# ChargerTimer_V3hack.net
KiCad netlist of a schematic drawn in EAGLE
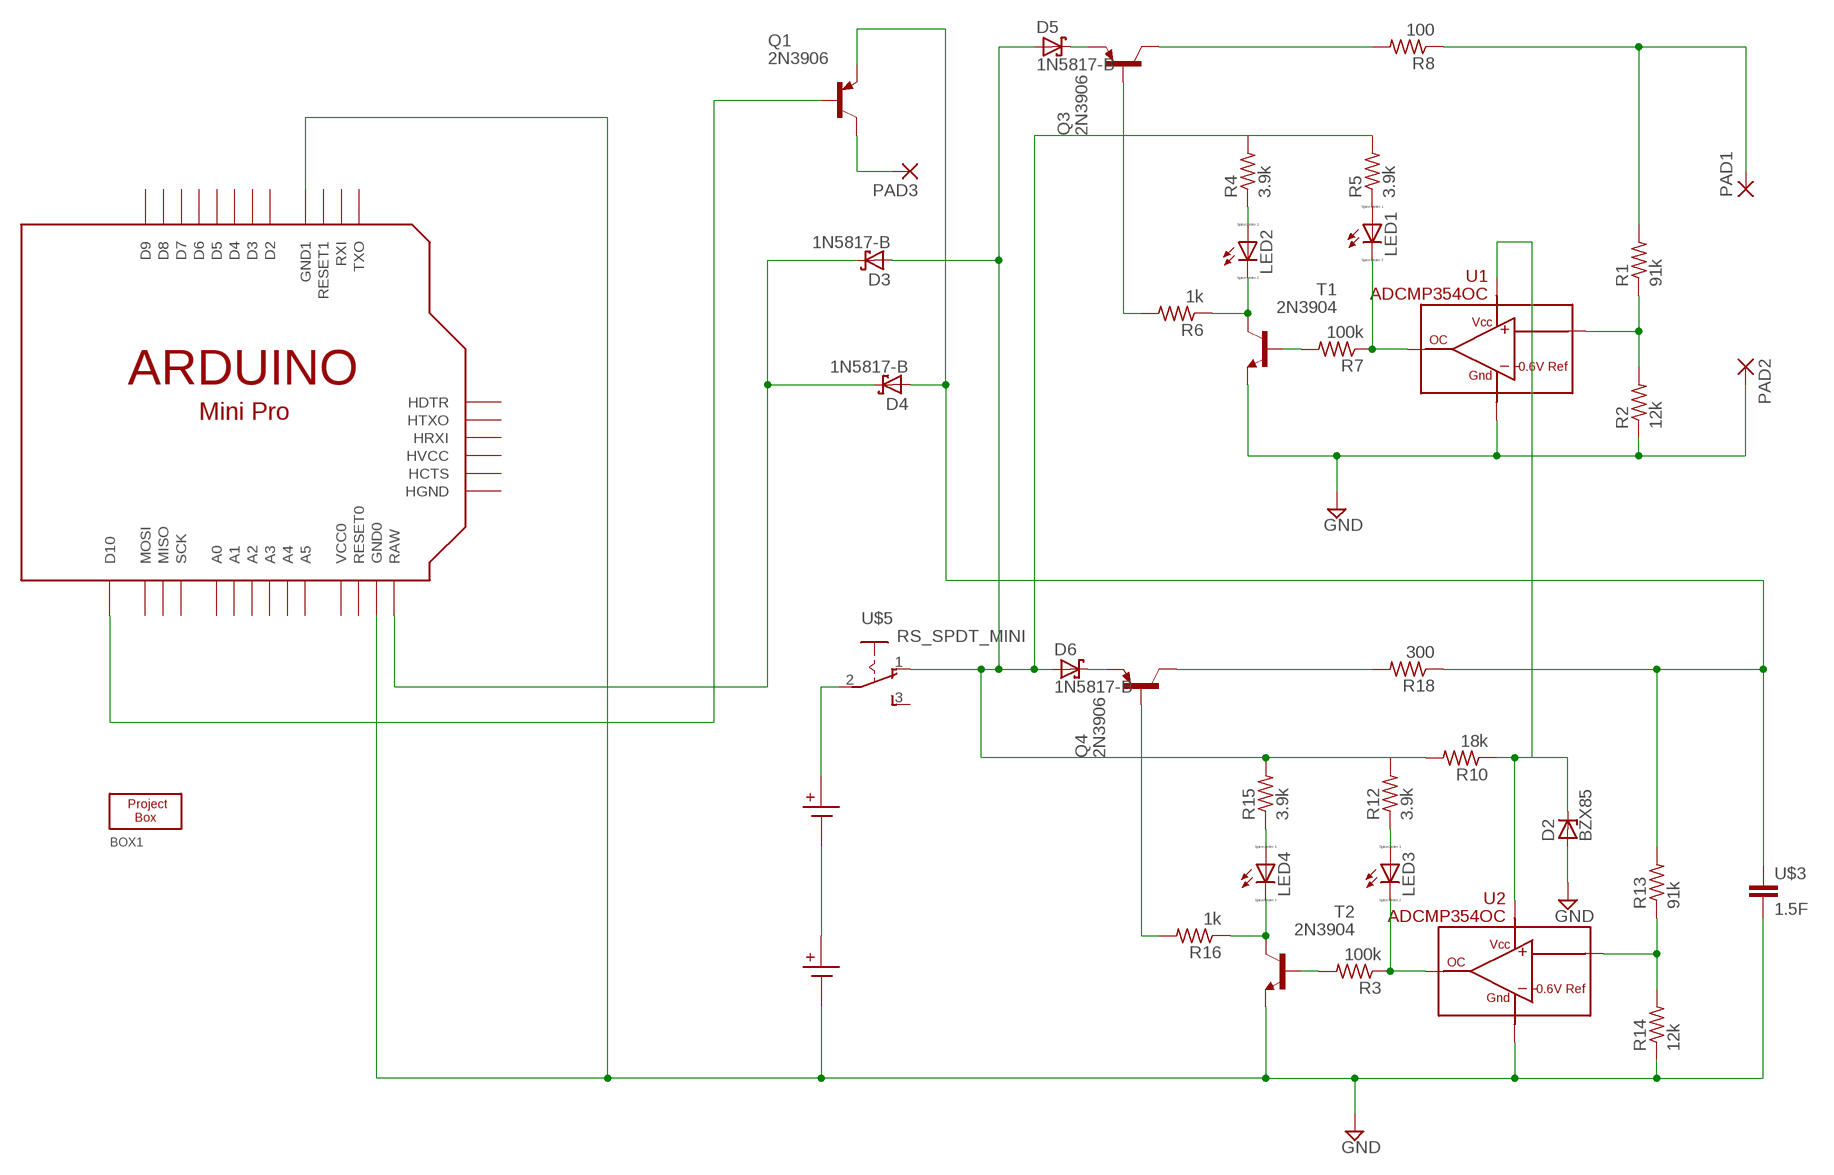
[diagram p0: schematic, sheet 1]

(export (version "E")
  (design (tool "Eeschema 10.0.6"))
  (components
    (comp (ref "BOX1")
      (value "RS_BOX_4IN")
      (footprint "eagle-import:RS_BOX_OUTLINE_4IN")
      (libsource (lib "eagle-import") (part "RS_BOX_4IN"))
    )
    (comp (ref "D2")
      (value "BZX85")
      (footprint "eagle-import:DO41Z10")
      (libsource (lib "eagle-import") (part "BZX85"))
    )
    (comp (ref "D3")
      (value "1N5817-B")
      (footprint "eagle-import:DO41-7.6")
      (libsource (lib "eagle-import") (part "1N5817-B"))
    )
    (comp (ref "D4")
      (value "1N5817-B")
      (footprint "eagle-import:DO41-7.6")
      (libsource (lib "eagle-import") (part "1N5817-B"))
    )
    (comp (ref "D5")
      (value "1N5817-B")
      (footprint "eagle-import:DO41-7.6")
      (libsource (lib "eagle-import") (part "1N5817-B"))
    )
    (comp (ref "D6")
      (value "1N5817-B")
      (footprint "eagle-import:DO41-7.6")
      (libsource (lib "eagle-import") (part "1N5817-B"))
    )
    (comp (ref "LED1")
      (value "LED_ELD260")
      (footprint "eagle-import:LED_LD260")
      (libsource (lib "eagle-import") (part "LED_ELD260"))
    )
    (comp (ref "LED2")
      (value "LED_ELD260")
      (footprint "eagle-import:LED_LD260")
      (libsource (lib "eagle-import") (part "LED_ELD260"))
    )
    (comp (ref "LED3")
      (value "LED_ELD260")
      (footprint "eagle-import:LED_LD260")
      (libsource (lib "eagle-import") (part "LED_ELD260"))
    )
    (comp (ref "LED4")
      (value "LED_ELD260")
      (footprint "eagle-import:LED_LD260")
      (libsource (lib "eagle-import") (part "LED_ELD260"))
    )
    (comp (ref "PAD1")
      (value "2,15/1,0")
      (footprint "eagle-import:2,15_1,0")
      (libsource (lib "eagle-import") (part "2,15/1,0"))
    )
    (comp (ref "PAD2")
      (value "2,15/1,0")
      (footprint "eagle-import:2,15_1,0")
      (libsource (lib "eagle-import") (part "2,15/1,0"))
    )
    (comp (ref "PAD3")
      (value "2,15/1,0")
      (footprint "eagle-import:2,15_1,0")
      (libsource (lib "eagle-import") (part "2,15/1,0"))
    )
    (comp (ref "Q1")
      (value "2N3906")
      (footprint "eagle-import:TO92")
      (libsource (lib "eagle-import") (part "2N3906"))
    )
    (comp (ref "Q3")
      (value "2N3906")
      (footprint "eagle-import:TO92")
      (libsource (lib "eagle-import") (part "2N3906"))
    )
    (comp (ref "Q4")
      (value "2N3906")
      (footprint "eagle-import:TO92")
      (libsource (lib "eagle-import") (part "2N3906"))
    )
    (comp (ref "R1")
      (value "91k")
      (footprint "eagle-import:0207_7")
      (libsource (lib "eagle-import") (part "R-US_0207/7"))
    )
    (comp (ref "R2")
      (value "12k")
      (footprint "eagle-import:0207_7")
      (libsource (lib "eagle-import") (part "R-US_0207/7"))
    )
    (comp (ref "R3")
      (value "100k")
      (footprint "eagle-import:0207_7")
      (libsource (lib "eagle-import") (part "R-US_0207/7"))
    )
    (comp (ref "R4")
      (value "3.9k")
      (footprint "eagle-import:0207_7")
      (libsource (lib "eagle-import") (part "R-US_0207/7"))
    )
    (comp (ref "R5")
      (value "3.9k")
      (footprint "eagle-import:0207_7")
      (libsource (lib "eagle-import") (part "R-US_0207/7"))
    )
    (comp (ref "R6")
      (value "1k")
      (footprint "eagle-import:0207_7")
      (libsource (lib "eagle-import") (part "R-US_0207/7"))
    )
    (comp (ref "R7")
      (value "100k")
      (footprint "eagle-import:0207_7")
      (libsource (lib "eagle-import") (part "R-US_0207/7"))
    )
    (comp (ref "R8")
      (value "100")
      (footprint "eagle-import:0207_7")
      (libsource (lib "eagle-import") (part "R-US_0207/7"))
    )
    (comp (ref "R10")
      (value "18k")
      (footprint "eagle-import:0207_7")
      (libsource (lib "eagle-import") (part "R-US_0207/7"))
    )
    (comp (ref "R12")
      (value "3.9k")
      (footprint "eagle-import:0207_7")
      (libsource (lib "eagle-import") (part "R-US_0207/7"))
    )
    (comp (ref "R13")
      (value "91k")
      (footprint "eagle-import:0207_7")
      (libsource (lib "eagle-import") (part "R-US_0207/7"))
    )
    (comp (ref "R14")
      (value "12k")
      (footprint "eagle-import:0207_7")
      (libsource (lib "eagle-import") (part "R-US_0207/7"))
    )
    (comp (ref "R15")
      (value "3.9k")
      (footprint "eagle-import:0207_7")
      (libsource (lib "eagle-import") (part "R-US_0207/7"))
    )
    (comp (ref "R16")
      (value "1k")
      (footprint "eagle-import:0207_7")
      (libsource (lib "eagle-import") (part "R-US_0207/7"))
    )
    (comp (ref "R18")
      (value "300")
      (footprint "eagle-import:0207_7")
      (libsource (lib "eagle-import") (part "R-US_0207/7"))
    )
    (comp (ref "T1")
      (value "2N3904")
      (footprint "eagle-import:TO92")
      (libsource (lib "eagle-import") (part "2N3904"))
    )
    (comp (ref "T2")
      (value "2N3904")
      (footprint "eagle-import:TO92")
      (libsource (lib "eagle-import") (part "2N3904"))
    )
    (comp (ref "U$1")
      (value "BH1000G")
      (footprint "eagle-import:BH1000G")
      (libsource (lib "eagle-import") (part "BH1000G"))
    )
    (comp (ref "U$2")
      (value "BH1000G")
      (footprint "eagle-import:BH1000G")
      (libsource (lib "eagle-import") (part "BH1000G"))
    )
    (comp (ref "U$3")
      (value "1.5F")
      (footprint "eagle-import:SUPERCAP1.0_0.85H")
      (libsource (lib "eagle-import") (part "C1000X850"))
    )
    (comp (ref "U$4")
      (value "ARDUINOMINI")
      (footprint "eagle-import:ARDUINOMINI")
      (libsource (lib "eagle-import") (part "ARDUINOMINI"))
    )
    (comp (ref "U$5")
      (value "RS_SPDT_MINI")
      (footprint "eagle-import:RS_SPDT_MINI")
      (libsource (lib "eagle-import") (part "RS_SPDT_MINI"))
    )
    (comp (ref "U1")
      (value "ADCMP354OC")
      (footprint "eagle-import:ADCMP35X")
      (libsource (lib "eagle-import") (part "ADCMP354OC"))
    )
    (comp (ref "U2")
      (value "ADCMP354OC")
      (footprint "eagle-import:ADCMP35X")
      (libsource (lib "eagle-import") (part "ADCMP354OC"))
    )
  )
  (nets
    (net (code "1") (name "GND") (class "Default")
      (node (ref "D2") (pin "A") (pinfunction "A_A") (pintype "passive"))
      (node (ref "PAD2") (pin "1") (pinfunction "P_1") (pintype "passive"))
      (node (ref "R14") (pin "1") (pinfunction "1_1") (pintype "passive"))
      (node (ref "R2") (pin "1") (pinfunction "1_1") (pintype "passive"))
      (node (ref "T1") (pin "3") (pinfunction "E_3") (pintype "passive"))
      (node (ref "T2") (pin "3") (pinfunction "E_3") (pintype "passive"))
      (node (ref "U$2") (pin "NEG$2") (pinfunction "P2_NEG$2") (pintype "power_in"))
      (node (ref "U$3") (pin "P$2") (pinfunction "2_P$2") (pintype "passive"))
      (node (ref "U$4") (pin "P$20") (pinfunction "GND0_P$20") (pintype "bidirectional"))
      (node (ref "U$4") (pin "P$9") (pinfunction "GND1_P$9") (pintype "bidirectional"))
      (node (ref "U1") (pin "P2") (pinfunction "GND_P2") (pintype "power_in"))
      (node (ref "U2") (pin "P2") (pinfunction "GND_P2") (pintype "power_in"))
    )
    (net (code "2") (name "Net-(LED1-C)") (class "Default")
      (node (ref "LED1") (pin "K") (pinfunction "C_K") (pintype "passive"))
      (node (ref "R7") (pin "1") (pinfunction "1_1") (pintype "passive"))
      (node (ref "U1") (pin "P3") (pinfunction "OUT_P3") (pintype "passive"))
    )
    (net (code "3") (name "Net-(LED1-PadA)") (class "Default")
      (node (ref "LED1") (pin "A") (pinfunction "A_A") (pintype "passive"))
      (node (ref "R5") (pin "1") (pinfunction "1_1") (pintype "passive"))
    )
    (net (code "4") (name "Net-(LED2-C)") (class "Default")
      (node (ref "LED2") (pin "K") (pinfunction "C_K") (pintype "passive"))
      (node (ref "R6") (pin "1") (pinfunction "1_1") (pintype "passive"))
      (node (ref "T1") (pin "1") (pinfunction "C_1") (pintype "passive"))
    )
    (net (code "5") (name "Net-(LED2-PadA)") (class "Default")
      (node (ref "LED2") (pin "A") (pinfunction "A_A") (pintype "passive"))
      (node (ref "R4") (pin "1") (pinfunction "1_1") (pintype "passive"))
    )
    (net (code "6") (name "Net-(LED3-C)") (class "Default")
      (node (ref "LED3") (pin "K") (pinfunction "C_K") (pintype "passive"))
      (node (ref "R3") (pin "1") (pinfunction "1_1") (pintype "passive"))
      (node (ref "U2") (pin "P3") (pinfunction "OUT_P3") (pintype "passive"))
    )
    (net (code "7") (name "Net-(LED3-PadA)") (class "Default")
      (node (ref "LED3") (pin "A") (pinfunction "A_A") (pintype "passive"))
      (node (ref "R12") (pin "1") (pinfunction "1_1") (pintype "passive"))
    )
    (net (code "8") (name "Net-(LED4-C)") (class "Default")
      (node (ref "LED4") (pin "K") (pinfunction "C_K") (pintype "passive"))
      (node (ref "R16") (pin "1") (pinfunction "1_1") (pintype "passive"))
      (node (ref "T2") (pin "1") (pinfunction "C_1") (pintype "passive"))
    )
    (net (code "9") (name "Net-(LED4-PadA)") (class "Default")
      (node (ref "LED4") (pin "A") (pinfunction "A_A") (pintype "passive"))
      (node (ref "R15") (pin "1") (pinfunction "1_1") (pintype "passive"))
    )
    (net (code "10") (name "Net-(PAD1-P)") (class "Default")
      (node (ref "PAD1") (pin "1") (pinfunction "P_1") (pintype "passive"))
      (node (ref "R1") (pin "2") (pinfunction "2_2") (pintype "passive"))
      (node (ref "R8") (pin "1") (pinfunction "1_1") (pintype "passive"))
    )
    (net (code "11") (name "Net-(PAD3-P)") (class "Default")
      (node (ref "PAD3") (pin "1") (pinfunction "P_1") (pintype "passive"))
      (node (ref "Q1") (pin "1") (pinfunction "C_1") (pintype "passive"))
    )
    (net (code "12") (name "Net-(Q1-B)") (class "Default")
      (node (ref "Q1") (pin "2") (pinfunction "B_2") (pintype "passive"))
      (node (ref "U$4") (pin "P$30") (pinfunction "D10_P$30") (pintype "bidirectional"))
    )
    (net (code "13") (name "Net-(Q1-E)") (class "Default")
      (node (ref "D4") (pin "A") (pinfunction "A_A") (pintype "passive"))
      (node (ref "Q1") (pin "3") (pinfunction "E_3") (pintype "passive"))
      (node (ref "R13") (pin "2") (pinfunction "2_2") (pintype "passive"))
      (node (ref "R18") (pin "1") (pinfunction "1_1") (pintype "passive"))
      (node (ref "U$3") (pin "P$1") (pinfunction "1_P$1") (pintype "passive"))
    )
    (net (code "14") (name "Net-(Q3-B)") (class "Default")
      (node (ref "Q3") (pin "2") (pinfunction "B_2") (pintype "passive"))
      (node (ref "R6") (pin "2") (pinfunction "2_2") (pintype "passive"))
    )
    (net (code "15") (name "Net-(Q3-C)") (class "Default")
      (node (ref "Q3") (pin "1") (pinfunction "C_1") (pintype "passive"))
      (node (ref "R8") (pin "2") (pinfunction "2_2") (pintype "passive"))
    )
    (net (code "16") (name "Net-(Q3-E)") (class "Default")
      (node (ref "D5") (pin "C") (pinfunction "C_C") (pintype "passive"))
      (node (ref "Q3") (pin "3") (pinfunction "E_3") (pintype "passive"))
    )
    (net (code "17") (name "Net-(Q4-B)") (class "Default")
      (node (ref "Q4") (pin "2") (pinfunction "B_2") (pintype "passive"))
      (node (ref "R16") (pin "2") (pinfunction "2_2") (pintype "passive"))
    )
    (net (code "18") (name "Net-(Q4-C)") (class "Default")
      (node (ref "Q4") (pin "1") (pinfunction "C_1") (pintype "passive"))
      (node (ref "R18") (pin "2") (pinfunction "2_2") (pintype "passive"))
    )
    (net (code "19") (name "Net-(Q4-E)") (class "Default")
      (node (ref "D6") (pin "C") (pinfunction "C_C") (pintype "passive"))
      (node (ref "Q4") (pin "3") (pinfunction "E_3") (pintype "passive"))
    )
    (net (code "20") (name "Net-(T1-B)") (class "Default")
      (node (ref "R7") (pin "2") (pinfunction "2_2") (pintype "passive"))
      (node (ref "T1") (pin "2") (pinfunction "B_2") (pintype "passive"))
    )
    (net (code "21") (name "Net-(T2-B)") (class "Default")
      (node (ref "R3") (pin "2") (pinfunction "2_2") (pintype "passive"))
      (node (ref "T2") (pin "2") (pinfunction "B_2") (pintype "passive"))
    )
    (net (code "22") (name "Net-(U$1-P1)") (class "Default")
      (node (ref "U$1") (pin "POS$1") (pinfunction "P1_POS$1") (pintype "power_in"))
      (node (ref "U$5") (pin "2") (pinfunction "P_2") (pintype "passive"))
    )
    (net (code "23") (name "Net-(U$1-P2)") (class "Default")
      (node (ref "U$1") (pin "NEG$2") (pinfunction "P2_NEG$2") (pintype "power_in"))
      (node (ref "U$2") (pin "POS$1") (pinfunction "P1_POS$1") (pintype "power_in"))
    )
    (net (code "24") (name "Net-(U$4-RAW)") (class "Default")
      (node (ref "D3") (pin "C") (pinfunction "C_C") (pintype "passive"))
      (node (ref "D4") (pin "C") (pinfunction "C_C") (pintype "passive"))
      (node (ref "U$4") (pin "P$19") (pinfunction "RAW_P$19") (pintype "bidirectional"))
    )
    (net (code "25") (name "Net-(U$5-O)") (class "Default")
      (node (ref "D3") (pin "A") (pinfunction "A_A") (pintype "passive"))
      (node (ref "D5") (pin "A") (pinfunction "A_A") (pintype "passive"))
      (node (ref "D6") (pin "A") (pinfunction "A_A") (pintype "passive"))
      (node (ref "R10") (pin "2") (pinfunction "2_2") (pintype "passive"))
      (node (ref "R12") (pin "2") (pinfunction "2_2") (pintype "passive"))
      (node (ref "R15") (pin "2") (pinfunction "2_2") (pintype "passive"))
      (node (ref "R4") (pin "2") (pinfunction "2_2") (pintype "passive"))
      (node (ref "R5") (pin "2") (pinfunction "2_2") (pintype "passive"))
      (node (ref "U$5") (pin "1") (pinfunction "O_1") (pintype "passive"))
    )
    (net (code "26") (name "Net-(U1-IN)") (class "Default")
      (node (ref "R1") (pin "1") (pinfunction "1_1") (pintype "passive"))
      (node (ref "R2") (pin "2") (pinfunction "2_2") (pintype "passive"))
      (node (ref "U1") (pin "P1") (pinfunction "IN_P1") (pintype "passive"))
    )
    (net (code "27") (name "Net-(U1-VCC)") (class "Default")
      (node (ref "D2") (pin "C") (pinfunction "C_C") (pintype "passive"))
      (node (ref "R10") (pin "1") (pinfunction "1_1") (pintype "passive"))
      (node (ref "U1") (pin "P4") (pinfunction "VCC_P4") (pintype "power_in"))
      (node (ref "U2") (pin "P4") (pinfunction "VCC_P4") (pintype "power_in"))
    )
    (net (code "28") (name "Net-(U2-IN)") (class "Default")
      (node (ref "R13") (pin "1") (pinfunction "1_1") (pintype "passive"))
      (node (ref "R14") (pin "2") (pinfunction "2_2") (pintype "passive"))
      (node (ref "U2") (pin "P1") (pinfunction "IN_P1") (pintype "passive"))
    )
    (net (code "29") (name "unconnected-(U$4-A0-PadP$26)") (class "Default")
      (node (ref "U$4") (pin "P$26") (pinfunction "A0_P$26") (pintype "bidirectional"))
    )
    (net (code "30") (name "unconnected-(U$4-A1-PadP$25)") (class "Default")
      (node (ref "U$4") (pin "P$25") (pinfunction "A1_P$25") (pintype "bidirectional"))
    )
    (net (code "31") (name "unconnected-(U$4-A2-PadP$24)") (class "Default")
      (node (ref "U$4") (pin "P$24") (pinfunction "A2_P$24") (pintype "bidirectional"))
    )
    (net (code "32") (name "unconnected-(U$4-A3-PadP$23)") (class "Default")
      (node (ref "U$4") (pin "P$23") (pinfunction "A3_P$23") (pintype "bidirectional"))
    )
    (net (code "33") (name "unconnected-(U$4-A4-PadP$34)") (class "Default")
      (node (ref "U$4") (pin "P$34") (pinfunction "A4_P$34") (pintype "bidirectional"))
    )
    (net (code "34") (name "unconnected-(U$4-A5-PadP$35)") (class "Default")
      (node (ref "U$4") (pin "P$35") (pinfunction "A5_P$35") (pintype "bidirectional"))
    )
    (net (code "35") (name "unconnected-(U$4-D2-PadP$8)") (class "Default")
      (node (ref "U$4") (pin "P$8") (pinfunction "D2_P$8") (pintype "bidirectional"))
    )
    (net (code "36") (name "unconnected-(U$4-D3-PadP$7)") (class "Default")
      (node (ref "U$4") (pin "P$7") (pinfunction "D3_P$7") (pintype "bidirectional"))
    )
    (net (code "37") (name "unconnected-(U$4-D4-PadP$6)") (class "Default")
      (node (ref "U$4") (pin "P$6") (pinfunction "D4_P$6") (pintype "bidirectional"))
    )
    (net (code "38") (name "unconnected-(U$4-D5-PadP$5)") (class "Default")
      (node (ref "U$4") (pin "P$5") (pinfunction "D5_P$5") (pintype "bidirectional"))
    )
    (net (code "39") (name "unconnected-(U$4-D6-PadP$4)") (class "Default")
      (node (ref "U$4") (pin "P$4") (pinfunction "D6_P$4") (pintype "bidirectional"))
    )
    (net (code "40") (name "unconnected-(U$4-D7-PadP$3)") (class "Default")
      (node (ref "U$4") (pin "P$3") (pinfunction "D7_P$3") (pintype "bidirectional"))
    )
    (net (code "41") (name "unconnected-(U$4-D8-PadP$2)") (class "Default")
      (node (ref "U$4") (pin "P$2") (pinfunction "D8_P$2") (pintype "bidirectional"))
    )
    (net (code "42") (name "unconnected-(U$4-D9-PadP$1)") (class "Default")
      (node (ref "U$4") (pin "P$1") (pinfunction "D9_P$1") (pintype "bidirectional"))
    )
    (net (code "43") (name "unconnected-(U$4-HCTS-PadP$17)") (class "Default")
      (node (ref "U$4") (pin "P$17") (pinfunction "HCTS_P$17") (pintype "bidirectional"))
    )
    (net (code "44") (name "unconnected-(U$4-HDTR-PadP$13)") (class "Default")
      (node (ref "U$4") (pin "P$13") (pinfunction "HDTR_P$13") (pintype "bidirectional"))
    )
    (net (code "45") (name "unconnected-(U$4-HGND-PadP$18)") (class "Default")
      (node (ref "U$4") (pin "P$18") (pinfunction "HGND_P$18") (pintype "bidirectional"))
    )
    (net (code "46") (name "unconnected-(U$4-HRXI-PadP$15)") (class "Default")
      (node (ref "U$4") (pin "P$15") (pinfunction "HRXI_P$15") (pintype "bidirectional"))
    )
    (net (code "47") (name "unconnected-(U$4-HTXO-PadP$14)") (class "Default")
      (node (ref "U$4") (pin "P$14") (pinfunction "HTXO_P$14") (pintype "bidirectional"))
    )
    (net (code "48") (name "unconnected-(U$4-HVCC-PadP$16)") (class "Default")
      (node (ref "U$4") (pin "P$16") (pinfunction "HVCC_P$16") (pintype "bidirectional"))
    )
    (net (code "49") (name "unconnected-(U$4-MISO-PadP$28)") (class "Default")
      (node (ref "U$4") (pin "P$28") (pinfunction "MISO_P$28") (pintype "bidirectional"))
    )
    (net (code "50") (name "unconnected-(U$4-MOSI-PadP$29)") (class "Default")
      (node (ref "U$4") (pin "P$29") (pinfunction "MOSI_P$29") (pintype "bidirectional"))
    )
    (net (code "51") (name "unconnected-(U$4-RESET0-PadP$21)") (class "Default")
      (node (ref "U$4") (pin "P$21") (pinfunction "RESET0_P$21") (pintype "bidirectional"))
    )
    (net (code "52") (name "unconnected-(U$4-RESET1-PadP$10)") (class "Default")
      (node (ref "U$4") (pin "P$10") (pinfunction "RESET1_P$10") (pintype "bidirectional"))
    )
    (net (code "53") (name "unconnected-(U$4-RXI-PadP$11)") (class "Default")
      (node (ref "U$4") (pin "P$11") (pinfunction "RXI_P$11") (pintype "bidirectional"))
    )
    (net (code "54") (name "unconnected-(U$4-SCK-PadP$27)") (class "Default")
      (node (ref "U$4") (pin "P$27") (pinfunction "SCK_P$27") (pintype "bidirectional"))
    )
    (net (code "55") (name "unconnected-(U$4-TXO-PadP$12)") (class "Default")
      (node (ref "U$4") (pin "P$12") (pinfunction "TXO_P$12") (pintype "bidirectional"))
    )
    (net (code "56") (name "unconnected-(U$4-VCC0-PadP$22)") (class "Default")
      (node (ref "U$4") (pin "P$22") (pinfunction "VCC0_P$22") (pintype "bidirectional"))
    )
    (net (code "57") (name "unconnected-(U$5-S-Pad3)") (class "Default")
      (node (ref "U$5") (pin "3") (pinfunction "S_3") (pintype "passive"))
    )
  )
)
